# voice-card-controller-1_1-w-logo.net
KiCad netlist of a schematic drawn in EAGLE
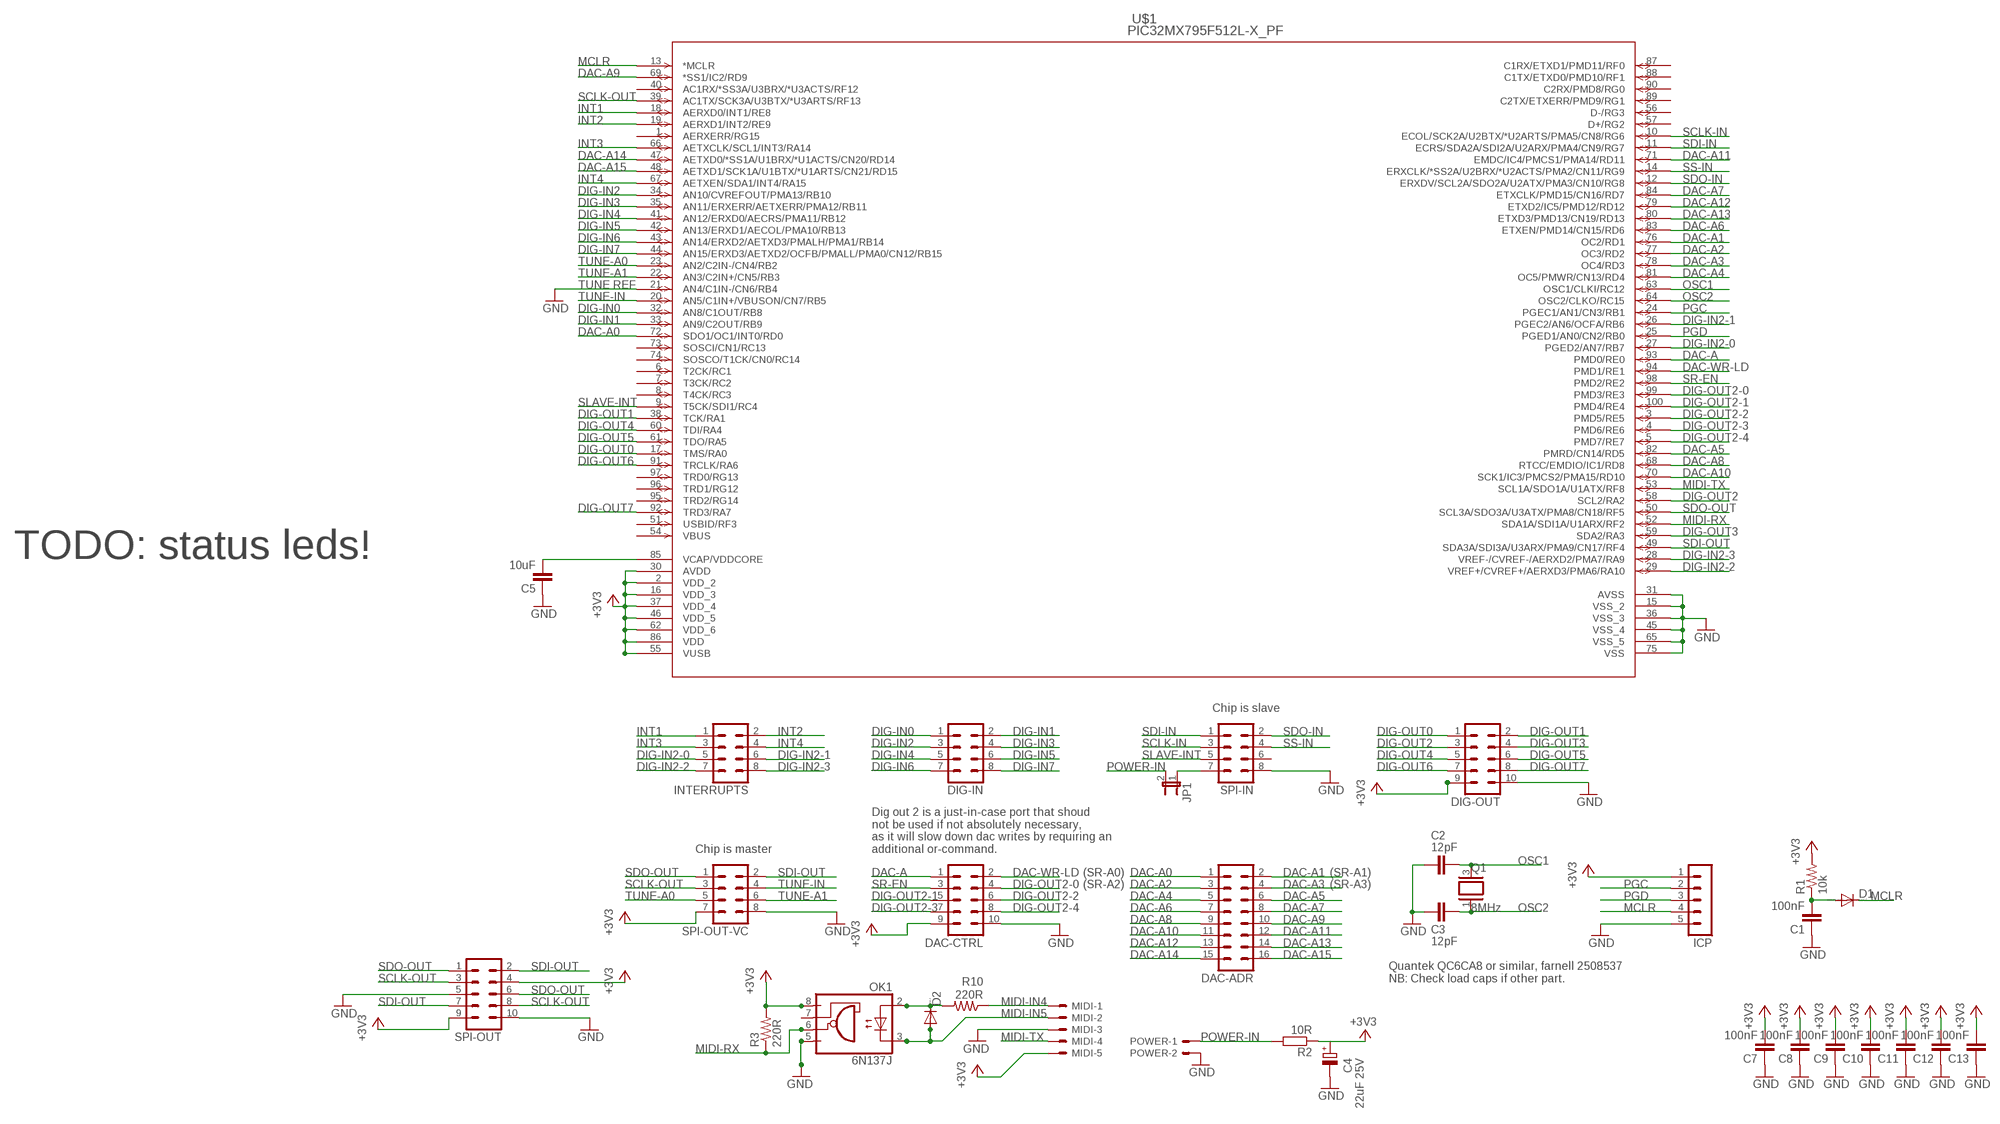
[diagram p0: schematic, sheet 1]

(export (version "E")
  (design (tool "Eeschema 10.0.6"))
  (components
    (comp (ref "C1")
      (value "100nF")
      (footprint "eagle-import:C0603")
      (libsource (lib "eagle-import") (part "C-EUC0603"))
    )
    (comp (ref "C2")
      (value "12pF")
      (footprint "eagle-import:C0603")
      (libsource (lib "eagle-import") (part "C-EUC0603"))
    )
    (comp (ref "C3")
      (value "12pF")
      (footprint "eagle-import:C0603")
      (libsource (lib "eagle-import") (part "C-EUC0603"))
    )
    (comp (ref "C4")
      (value "22uF 25V")
      (footprint "eagle-import:E2,5-5")
      (libsource (lib "eagle-import") (part "CPOL-EUE2.5-5"))
    )
    (comp (ref "C5")
      (value "10uF")
      (footprint "eagle-import:C0805")
      (libsource (lib "eagle-import") (part "C-EUC0805"))
    )
    (comp (ref "C7")
      (value "100nF")
      (footprint "eagle-import:C0603")
      (libsource (lib "eagle-import") (part "C-EUC0603"))
    )
    (comp (ref "C8")
      (value "100nF")
      (footprint "eagle-import:C0603")
      (libsource (lib "eagle-import") (part "C-EUC0603"))
    )
    (comp (ref "C9")
      (value "100nF")
      (footprint "eagle-import:C0603")
      (libsource (lib "eagle-import") (part "C-EUC0603"))
    )
    (comp (ref "C10")
      (value "100nF")
      (footprint "eagle-import:C0603")
      (libsource (lib "eagle-import") (part "C-EUC0603"))
    )
    (comp (ref "C11")
      (value "100nF")
      (footprint "eagle-import:C0603")
      (libsource (lib "eagle-import") (part "C-EUC0603"))
    )
    (comp (ref "C12")
      (value "100nF")
      (footprint "eagle-import:C0603")
      (libsource (lib "eagle-import") (part "C-EUC0603"))
    )
    (comp (ref "C13")
      (value "100nF")
      (footprint "eagle-import:C0603")
      (libsource (lib "eagle-import") (part "C-EUC0603"))
    )
    (comp (ref "D1")
      (value "DIODE-SOD80C")
      (footprint "eagle-import:SOD80C")
      (libsource (lib "eagle-import") (part "DIODE-SOD80C"))
    )
    (comp (ref "D2")
      (value "DIODE-SOD80C")
      (footprint "eagle-import:SOD80C")
      (libsource (lib "eagle-import") (part "DIODE-SOD80C"))
    )
    (comp (ref "DAC-ADR")
      (value "MA08-2J")
      (footprint "eagle-import:MA08-2J")
      (libsource (lib "eagle-import") (part "MA08-2J"))
    )
    (comp (ref "DAC-CTRL")
      (value "MA05-2J")
      (footprint "eagle-import:MA05-2J")
      (libsource (lib "eagle-import") (part "MA05-2J"))
    )
    (comp (ref "DIG-IN")
      (value "MA04-2J")
      (footprint "eagle-import:MA04-2J")
      (libsource (lib "eagle-import") (part "MA04-2J"))
    )
    (comp (ref "DIG-OUT")
      (value "MA05-2J")
      (footprint "eagle-import:MA05-2J")
      (libsource (lib "eagle-import") (part "MA05-2J"))
    )
    (comp (ref "ICP")
      (value "MA05-1")
      (footprint "eagle-import:MA05-1")
      (libsource (lib "eagle-import") (part "MA05-1"))
    )
    (comp (ref "INTERRUPTS")
      (value "MA04-2J")
      (footprint "eagle-import:MA04-2J")
      (libsource (lib "eagle-import") (part "MA04-2J"))
    )
    (comp (ref "JP1")
      (value "JP1E")
      (footprint "eagle-import:JP1")
      (libsource (lib "eagle-import") (part "JP1E"))
    )
    (comp (ref "MIDI")
      (value "22-23-2051")
      (footprint "eagle-import:22-23-2051")
      (fields (field (name "MF") "MOLEX"))
      (libsource (lib "eagle-import") (part "22-23-2051"))
    )
    (comp (ref "OK1")
      (value "6N137J")
      (footprint "eagle-import:DIL08-J")
      (libsource (lib "eagle-import") (part "6N137J"))
    )
    (comp (ref "POWER")
      (value "22-23-2021")
      (footprint "eagle-import:22-23-2021")
      (fields (field (name "MF") "MOLEX"))
      (libsource (lib "eagle-import") (part "22-23-2021"))
    )
    (comp (ref "Q1")
      (value "8MHz")
      (footprint "eagle-import:CTS406J")
      (libsource (lib "eagle-import") (part "XTAL-J"))
    )
    (comp (ref "R1")
      (value "10k")
      (footprint "eagle-import:R0805")
      (libsource (lib "eagle-import") (part "R-US_R0805"))
    )
    (comp (ref "R2")
      (value "10R")
      (footprint "eagle-import:0207_7")
      (libsource (lib "eagle-import") (part "R-EU_0207/7"))
    )
    (comp (ref "R3")
      (value "220R")
      (footprint "eagle-import:R0805")
      (libsource (lib "eagle-import") (part "R-US_R0805"))
    )
    (comp (ref "R10")
      (value "220R")
      (footprint "eagle-import:R0805")
      (libsource (lib "eagle-import") (part "R-US_R0805"))
    )
    (comp (ref "SPI-IN")
      (value "MA04-2J")
      (footprint "eagle-import:MA04-2J")
      (libsource (lib "eagle-import") (part "MA04-2J"))
    )
    (comp (ref "SPI-OUT")
      (value "MA05-2J")
      (footprint "eagle-import:MA05-2J")
      (libsource (lib "eagle-import") (part "MA05-2J"))
    )
    (comp (ref "SPI-OUT-VC")
      (value "MA04-2J")
      (footprint "eagle-import:MA04-2J")
      (libsource (lib "eagle-import") (part "MA04-2J"))
    )
    (comp (ref "U$1")
      (value "PIC32MX795F512L-X_PF")
      (footprint "eagle-import:TQFP100_14X14MC")
      (libsource (lib "eagle-import") (part "PIC32MX795F512L-X_PF"))
    )
  )
  (nets
    (net (code "1") (name "+3V3") (class "Default")
      (node (ref "C10") (pin "2") (pinfunction "2_2") (pintype "passive"))
      (node (ref "C11") (pin "2") (pinfunction "2_2") (pintype "passive"))
      (node (ref "C12") (pin "2") (pinfunction "2_2") (pintype "passive"))
      (node (ref "C13") (pin "2") (pinfunction "2_2") (pintype "passive"))
      (node (ref "C4") (pin "+") (pinfunction "+_+") (pintype "passive"))
      (node (ref "C7") (pin "2") (pinfunction "2_2") (pintype "passive"))
      (node (ref "C8") (pin "2") (pinfunction "2_2") (pintype "passive"))
      (node (ref "C9") (pin "2") (pinfunction "2_2") (pintype "passive"))
      (node (ref "DAC-CTRL") (pin "9") (pinfunction "9_9") (pintype "passive"))
      (node (ref "DIG-OUT") (pin "9") (pinfunction "9_9") (pintype "passive"))
      (node (ref "ICP") (pin "1") (pinfunction "1_1") (pintype "passive"))
      (node (ref "MIDI") (pin "5") (pinfunction "S_5") (pintype "passive"))
      (node (ref "OK1") (pin "8") (pinfunction "VCC_8") (pintype "passive"))
      (node (ref "R1") (pin "2") (pinfunction "2_2") (pintype "passive"))
      (node (ref "R2") (pin "1") (pinfunction "1_1") (pintype "passive"))
      (node (ref "R3") (pin "2") (pinfunction "2_2") (pintype "passive"))
      (node (ref "SPI-OUT") (pin "4") (pinfunction "4_4") (pintype "passive"))
      (node (ref "SPI-OUT") (pin "9") (pinfunction "9_9") (pintype "passive"))
      (node (ref "SPI-OUT-VC") (pin "7") (pinfunction "7_7") (pintype "passive"))
      (node (ref "U$1") (pin "16") (pinfunction "VDD_3_16") (pintype "power_in"))
      (node (ref "U$1") (pin "2") (pinfunction "VDD_2_2") (pintype "power_in"))
      (node (ref "U$1") (pin "30") (pinfunction "AVDD_30") (pintype "power_in"))
      (node (ref "U$1") (pin "37") (pinfunction "VDD_4_37") (pintype "power_in"))
      (node (ref "U$1") (pin "46") (pinfunction "VDD_5_46") (pintype "power_in"))
      (node (ref "U$1") (pin "55") (pinfunction "VUSB_55") (pintype "power_in"))
      (node (ref "U$1") (pin "62") (pinfunction "VDD_6_62") (pintype "power_in"))
      (node (ref "U$1") (pin "86") (pinfunction "VDD_86") (pintype "power_in"))
    )
    (net (code "2") (name "/DAC-A") (class "Default")
      (node (ref "DAC-CTRL") (pin "1") (pinfunction "1_1") (pintype "passive"))
      (node (ref "U$1") (pin "93") (pinfunction "PMD0/RE0_93") (pintype "bidirectional"))
    )
    (net (code "3") (name "/DAC-A0") (class "Default")
      (node (ref "DAC-ADR") (pin "1") (pinfunction "1_1") (pintype "passive"))
      (node (ref "U$1") (pin "72") (pinfunction "SDO1/OC1/INT0/RD0_72") (pintype "bidirectional"))
    )
    (net (code "4") (name "/DAC-A1") (class "Default")
      (node (ref "DAC-ADR") (pin "2") (pinfunction "2_2") (pintype "passive"))
      (node (ref "U$1") (pin "76") (pinfunction "OC2/RD1_76") (pintype "bidirectional"))
    )
    (net (code "5") (name "/DAC-A2") (class "Default")
      (node (ref "DAC-ADR") (pin "3") (pinfunction "3_3") (pintype "passive"))
      (node (ref "U$1") (pin "77") (pinfunction "OC3/RD2_77") (pintype "bidirectional"))
    )
    (net (code "6") (name "/DAC-A3") (class "Default")
      (node (ref "DAC-ADR") (pin "4") (pinfunction "4_4") (pintype "passive"))
      (node (ref "U$1") (pin "78") (pinfunction "OC4/RD3_78") (pintype "bidirectional"))
    )
    (net (code "7") (name "/DAC-A4") (class "Default")
      (node (ref "DAC-ADR") (pin "5") (pinfunction "5_5") (pintype "passive"))
      (node (ref "U$1") (pin "81") (pinfunction "OC5/PMWR/CN13/RD4_81") (pintype "bidirectional"))
    )
    (net (code "8") (name "/DAC-A5") (class "Default")
      (node (ref "DAC-ADR") (pin "6") (pinfunction "6_6") (pintype "passive"))
      (node (ref "U$1") (pin "82") (pinfunction "PMRD/CN14/RD5_82") (pintype "bidirectional"))
    )
    (net (code "9") (name "/DAC-A6") (class "Default")
      (node (ref "DAC-ADR") (pin "7") (pinfunction "7_7") (pintype "passive"))
      (node (ref "U$1") (pin "83") (pinfunction "ETXEN/PMD14/CN15/RD6_83") (pintype "bidirectional"))
    )
    (net (code "10") (name "/DAC-A7") (class "Default")
      (node (ref "DAC-ADR") (pin "8") (pinfunction "8_8") (pintype "passive"))
      (node (ref "U$1") (pin "84") (pinfunction "ETXCLK/PMD15/CN16/RD7_84") (pintype "bidirectional"))
    )
    (net (code "11") (name "/DAC-A8") (class "Default")
      (node (ref "DAC-ADR") (pin "9") (pinfunction "9_9") (pintype "passive"))
      (node (ref "U$1") (pin "68") (pinfunction "RTCC/EMDIO/IC1/RD8_68") (pintype "bidirectional"))
    )
    (net (code "12") (name "/DAC-A9") (class "Default")
      (node (ref "DAC-ADR") (pin "10") (pinfunction "10_10") (pintype "passive"))
      (node (ref "U$1") (pin "69") (pinfunction "*SS1/IC2/RD9_69") (pintype "bidirectional"))
    )
    (net (code "13") (name "/DAC-A10") (class "Default")
      (node (ref "DAC-ADR") (pin "11") (pinfunction "11_11") (pintype "passive"))
      (node (ref "U$1") (pin "70") (pinfunction "SCK1/IC3/PMCS2/PMA15/RD10_70") (pintype "bidirectional"))
    )
    (net (code "14") (name "/DAC-A11") (class "Default")
      (node (ref "DAC-ADR") (pin "12") (pinfunction "12_12") (pintype "passive"))
      (node (ref "U$1") (pin "71") (pinfunction "EMDC/IC4/PMCS1/PMA14/RD11_71") (pintype "bidirectional"))
    )
    (net (code "15") (name "/DAC-A12") (class "Default")
      (node (ref "DAC-ADR") (pin "13") (pinfunction "13_13") (pintype "passive"))
      (node (ref "U$1") (pin "79") (pinfunction "ETXD2/IC5/PMD12/RD12_79") (pintype "bidirectional"))
    )
    (net (code "16") (name "/DAC-A13") (class "Default")
      (node (ref "DAC-ADR") (pin "14") (pinfunction "14_14") (pintype "passive"))
      (node (ref "U$1") (pin "80") (pinfunction "ETXD3/PMD13/CN19/RD13_80") (pintype "bidirectional"))
    )
    (net (code "17") (name "/DAC-A14") (class "Default")
      (node (ref "DAC-ADR") (pin "15") (pinfunction "15_15") (pintype "passive"))
      (node (ref "U$1") (pin "47") (pinfunction "AETXD0/*SS1A/U1BRX/*U1ACTS/CN20/RD14_47") (pintype "bidirectional"))
    )
    (net (code "18") (name "/DAC-A15") (class "Default")
      (node (ref "DAC-ADR") (pin "16") (pinfunction "16_16") (pintype "passive"))
      (node (ref "U$1") (pin "48") (pinfunction "AETXD1/SCK1A/U1BTX/*U1ARTS/CN21/RD15_48") (pintype "bidirectional"))
    )
    (net (code "19") (name "/DAC-WR-LD") (class "Default")
      (node (ref "DAC-CTRL") (pin "2") (pinfunction "2_2") (pintype "passive"))
      (node (ref "U$1") (pin "94") (pinfunction "PMD1/RE1_94") (pintype "bidirectional"))
    )
    (net (code "20") (name "/DIG-IN0") (class "Default")
      (node (ref "DIG-IN") (pin "1") (pinfunction "1_1") (pintype "passive"))
      (node (ref "U$1") (pin "32") (pinfunction "AN8/C1OUT/RB8_32") (pintype "bidirectional"))
    )
    (net (code "21") (name "/DIG-IN1") (class "Default")
      (node (ref "DIG-IN") (pin "2") (pinfunction "2_2") (pintype "passive"))
      (node (ref "U$1") (pin "33") (pinfunction "AN9/C2OUT/RB9_33") (pintype "bidirectional"))
    )
    (net (code "22") (name "/DIG-IN2") (class "Default")
      (node (ref "DIG-IN") (pin "3") (pinfunction "3_3") (pintype "passive"))
      (node (ref "U$1") (pin "34") (pinfunction "AN10/CVREFOUT/PMA13/RB10_34") (pintype "bidirectional"))
    )
    (net (code "23") (name "/DIG-IN2-0") (class "Default")
      (node (ref "INTERRUPTS") (pin "5") (pinfunction "5_5") (pintype "passive"))
      (node (ref "U$1") (pin "27") (pinfunction "PGED2/AN7/RB7_27") (pintype "bidirectional"))
    )
    (net (code "24") (name "/DIG-IN2-1") (class "Default")
      (node (ref "INTERRUPTS") (pin "6") (pinfunction "6_6") (pintype "passive"))
      (node (ref "U$1") (pin "26") (pinfunction "PGEC2/AN6/OCFA/RB6_26") (pintype "bidirectional"))
    )
    (net (code "25") (name "/DIG-IN2-2") (class "Default")
      (node (ref "INTERRUPTS") (pin "7") (pinfunction "7_7") (pintype "passive"))
      (node (ref "U$1") (pin "29") (pinfunction "VREF+/CVREF+/AERXD3/PMA6/RA10_29") (pintype "bidirectional"))
    )
    (net (code "26") (name "/DIG-IN2-3") (class "Default")
      (node (ref "INTERRUPTS") (pin "8") (pinfunction "8_8") (pintype "passive"))
      (node (ref "U$1") (pin "28") (pinfunction "VREF-/CVREF-/AERXD2/PMA7/RA9_28") (pintype "bidirectional"))
    )
    (net (code "27") (name "/DIG-IN3") (class "Default")
      (node (ref "DIG-IN") (pin "4") (pinfunction "4_4") (pintype "passive"))
      (node (ref "U$1") (pin "35") (pinfunction "AN11/ERXERR/AETXERR/PMA12/RB11_35") (pintype "bidirectional"))
    )
    (net (code "28") (name "/DIG-IN4") (class "Default")
      (node (ref "DIG-IN") (pin "5") (pinfunction "5_5") (pintype "passive"))
      (node (ref "U$1") (pin "41") (pinfunction "AN12/ERXD0/AECRS/PMA11/RB12_41") (pintype "bidirectional"))
    )
    (net (code "29") (name "/DIG-IN5") (class "Default")
      (node (ref "DIG-IN") (pin "6") (pinfunction "6_6") (pintype "passive"))
      (node (ref "U$1") (pin "42") (pinfunction "AN13/ERXD1/AECOL/PMA10/RB13_42") (pintype "bidirectional"))
    )
    (net (code "30") (name "/DIG-IN6") (class "Default")
      (node (ref "DIG-IN") (pin "7") (pinfunction "7_7") (pintype "passive"))
      (node (ref "U$1") (pin "43") (pinfunction "AN14/ERXD2/AETXD3/PMALH/PMA1/RB14_43") (pintype "bidirectional"))
    )
    (net (code "31") (name "/DIG-IN7") (class "Default")
      (node (ref "DIG-IN") (pin "8") (pinfunction "8_8") (pintype "passive"))
      (node (ref "U$1") (pin "44") (pinfunction "AN15/ERXD3/AETXD2/OCFB/PMALL/PMA0/CN12/RB15_44") (pintype "bidirectional"))
    )
    (net (code "32") (name "/DIG-OUT0") (class "Default")
      (node (ref "DIG-OUT") (pin "1") (pinfunction "1_1") (pintype "passive"))
      (node (ref "U$1") (pin "17") (pinfunction "TMS/RA0_17") (pintype "bidirectional"))
    )
    (net (code "33") (name "/DIG-OUT1") (class "Default")
      (node (ref "DIG-OUT") (pin "2") (pinfunction "2_2") (pintype "passive"))
      (node (ref "U$1") (pin "38") (pinfunction "TCK/RA1_38") (pintype "bidirectional"))
    )
    (net (code "34") (name "/DIG-OUT2") (class "Default")
      (node (ref "DIG-OUT") (pin "3") (pinfunction "3_3") (pintype "passive"))
      (node (ref "U$1") (pin "58") (pinfunction "SCL2/RA2_58") (pintype "bidirectional"))
    )
    (net (code "35") (name "/DIG-OUT2-0") (class "Default")
      (node (ref "DAC-CTRL") (pin "4") (pinfunction "4_4") (pintype "passive"))
      (node (ref "U$1") (pin "99") (pinfunction "PMD3/RE3_99") (pintype "bidirectional"))
    )
    (net (code "36") (name "/DIG-OUT2-1") (class "Default")
      (node (ref "DAC-CTRL") (pin "5") (pinfunction "5_5") (pintype "passive"))
      (node (ref "U$1") (pin "100") (pinfunction "PMD4/RE4_100") (pintype "bidirectional"))
    )
    (net (code "37") (name "/DIG-OUT2-2") (class "Default")
      (node (ref "DAC-CTRL") (pin "6") (pinfunction "6_6") (pintype "passive"))
      (node (ref "U$1") (pin "3") (pinfunction "PMD5/RE5_3") (pintype "bidirectional"))
    )
    (net (code "38") (name "/DIG-OUT2-3") (class "Default")
      (node (ref "DAC-CTRL") (pin "7") (pinfunction "7_7") (pintype "passive"))
      (node (ref "U$1") (pin "4") (pinfunction "PMD6/RE6_4") (pintype "bidirectional"))
    )
    (net (code "39") (name "/DIG-OUT2-4") (class "Default")
      (node (ref "DAC-CTRL") (pin "8") (pinfunction "8_8") (pintype "passive"))
      (node (ref "U$1") (pin "5") (pinfunction "PMD7/RE7_5") (pintype "bidirectional"))
    )
    (net (code "40") (name "/DIG-OUT3") (class "Default")
      (node (ref "DIG-OUT") (pin "4") (pinfunction "4_4") (pintype "passive"))
      (node (ref "U$1") (pin "59") (pinfunction "SDA2/RA3_59") (pintype "bidirectional"))
    )
    (net (code "41") (name "/DIG-OUT4") (class "Default")
      (node (ref "DIG-OUT") (pin "5") (pinfunction "5_5") (pintype "passive"))
      (node (ref "U$1") (pin "60") (pinfunction "TDI/RA4_60") (pintype "bidirectional"))
    )
    (net (code "42") (name "/DIG-OUT5") (class "Default")
      (node (ref "DIG-OUT") (pin "6") (pinfunction "6_6") (pintype "passive"))
      (node (ref "U$1") (pin "61") (pinfunction "TDO/RA5_61") (pintype "bidirectional"))
    )
    (net (code "43") (name "/DIG-OUT6") (class "Default")
      (node (ref "DIG-OUT") (pin "7") (pinfunction "7_7") (pintype "passive"))
      (node (ref "U$1") (pin "91") (pinfunction "TRCLK/RA6_91") (pintype "bidirectional"))
    )
    (net (code "44") (name "/DIG-OUT7") (class "Default")
      (node (ref "DIG-OUT") (pin "8") (pinfunction "8_8") (pintype "passive"))
      (node (ref "U$1") (pin "92") (pinfunction "TRD3/RA7_92") (pintype "bidirectional"))
    )
    (net (code "45") (name "/INT1") (class "Default")
      (node (ref "INTERRUPTS") (pin "1") (pinfunction "1_1") (pintype "passive"))
      (node (ref "U$1") (pin "18") (pinfunction "AERXD0/INT1/RE8_18") (pintype "bidirectional"))
    )
    (net (code "46") (name "/INT2") (class "Default")
      (node (ref "INTERRUPTS") (pin "2") (pinfunction "2_2") (pintype "passive"))
      (node (ref "U$1") (pin "19") (pinfunction "AERXD1/INT2/RE9_19") (pintype "bidirectional"))
    )
    (net (code "47") (name "/INT3") (class "Default")
      (node (ref "INTERRUPTS") (pin "3") (pinfunction "3_3") (pintype "passive"))
      (node (ref "U$1") (pin "66") (pinfunction "AETXCLK/SCL1/INT3/RA14_66") (pintype "bidirectional"))
    )
    (net (code "48") (name "/INT4") (class "Default")
      (node (ref "INTERRUPTS") (pin "4") (pinfunction "4_4") (pintype "passive"))
      (node (ref "U$1") (pin "67") (pinfunction "AETXEN/SDA1/INT4/RA15_67") (pintype "bidirectional"))
    )
    (net (code "49") (name "/MCLR") (class "Default")
      (node (ref "D1") (pin "C") (pinfunction "C_C") (pintype "passive"))
      (node (ref "ICP") (pin "4") (pinfunction "4_4") (pintype "passive"))
      (node (ref "U$1") (pin "13") (pinfunction "*MCLR_13") (pintype "input"))
    )
    (net (code "50") (name "/MIDI-IN4") (class "Default")
      (node (ref "MIDI") (pin "1") (pinfunction "S_1") (pintype "passive"))
      (node (ref "R10") (pin "1") (pinfunction "1_1") (pintype "passive"))
    )
    (net (code "51") (name "/MIDI-IN5") (class "Default")
      (node (ref "D2") (pin "A") (pinfunction "A_A") (pintype "passive"))
      (node (ref "MIDI") (pin "2") (pinfunction "S_2") (pintype "passive"))
      (node (ref "OK1") (pin "3") (pinfunction "C_3") (pintype "passive"))
    )
    (net (code "52") (name "/MIDI-RX") (class "Default")
      (node (ref "OK1") (pin "6") (pinfunction "VO_6") (pintype "passive"))
      (node (ref "R3") (pin "1") (pinfunction "1_1") (pintype "passive"))
      (node (ref "U$1") (pin "52") (pinfunction "SDA1A/SDI1A/U1ARX/RF2_52") (pintype "bidirectional"))
    )
    (net (code "53") (name "/MIDI-TX") (class "Default")
      (node (ref "MIDI") (pin "4") (pinfunction "S_4") (pintype "passive"))
      (node (ref "U$1") (pin "53") (pinfunction "SCL1A/SDO1A/U1ATX/RF8_53") (pintype "bidirectional"))
    )
    (net (code "54") (name "/OSC1") (class "Default")
      (node (ref "C2") (pin "1") (pinfunction "1_1") (pintype "passive"))
      (node (ref "Q1") (pin "3") (pinfunction "2_3") (pintype "passive"))
      (node (ref "U$1") (pin "63") (pinfunction "OSC1/CLKI/RC12_63") (pintype "bidirectional"))
    )
    (net (code "55") (name "/OSC2") (class "Default")
      (node (ref "C3") (pin "1") (pinfunction "1_1") (pintype "passive"))
      (node (ref "Q1") (pin "1") (pinfunction "1_1") (pintype "passive"))
      (node (ref "U$1") (pin "64") (pinfunction "OSC2/CLKO/RC15_64") (pintype "bidirectional"))
    )
    (net (code "56") (name "/PGC") (class "Default")
      (node (ref "ICP") (pin "2") (pinfunction "2_2") (pintype "passive"))
      (node (ref "U$1") (pin "24") (pinfunction "PGEC1/AN1/CN3/RB1_24") (pintype "bidirectional"))
    )
    (net (code "57") (name "/PGD") (class "Default")
      (node (ref "ICP") (pin "3") (pinfunction "3_3") (pintype "passive"))
      (node (ref "U$1") (pin "25") (pinfunction "PGED1/AN0/CN2/RB0_25") (pintype "bidirectional"))
    )
    (net (code "58") (name "/POWER-IN") (class "Default")
      (node (ref "JP1") (pin "2") (pinfunction "2_2") (pintype "passive"))
      (node (ref "POWER") (pin "1") (pinfunction "S_1") (pintype "passive"))
      (node (ref "R2") (pin "2") (pinfunction "2_2") (pintype "passive"))
    )
    (net (code "59") (name "/SCLK-IN") (class "Default")
      (node (ref "SPI-IN") (pin "3") (pinfunction "3_3") (pintype "passive"))
      (node (ref "U$1") (pin "10") (pinfunction "ECOL/SCK2A/U2BTX/*U2ARTS/PMA5/CN8/RG6_10") (pintype "bidirectional"))
    )
    (net (code "60") (name "/SCLK-OUT") (class "Default")
      (node (ref "SPI-OUT") (pin "3") (pinfunction "3_3") (pintype "passive"))
      (node (ref "SPI-OUT") (pin "8") (pinfunction "8_8") (pintype "passive"))
      (node (ref "SPI-OUT-VC") (pin "3") (pinfunction "3_3") (pintype "passive"))
      (node (ref "U$1") (pin "39") (pinfunction "AC1TX/SCK3A/U3BTX/*U3ARTS/RF13_39") (pintype "bidirectional"))
    )
    (net (code "61") (name "/SDI-IN") (class "Default")
      (node (ref "SPI-IN") (pin "1") (pinfunction "1_1") (pintype "passive"))
      (node (ref "U$1") (pin "11") (pinfunction "ECRS/SDA2A/SDI2A/U2ARX/PMA4/CN9/RG7_11") (pintype "bidirectional"))
    )
    (net (code "62") (name "/SDI-OUT") (class "Default")
      (node (ref "SPI-OUT") (pin "2") (pinfunction "2_2") (pintype "passive"))
      (node (ref "SPI-OUT") (pin "7") (pinfunction "7_7") (pintype "passive"))
      (node (ref "SPI-OUT-VC") (pin "2") (pinfunction "2_2") (pintype "passive"))
      (node (ref "U$1") (pin "49") (pinfunction "SDA3A/SDI3A/U3ARX/PMA9/CN17/RF4_49") (pintype "bidirectional"))
    )
    (net (code "63") (name "/SDO-IN") (class "Default")
      (node (ref "SPI-IN") (pin "2") (pinfunction "2_2") (pintype "passive"))
      (node (ref "U$1") (pin "12") (pinfunction "ERXDV/SCL2A/SDO2A/U2ATX/PMA3/CN10/RG8_12") (pintype "bidirectional"))
    )
    (net (code "64") (name "/SDO-OUT") (class "Default")
      (node (ref "SPI-OUT") (pin "1") (pinfunction "1_1") (pintype "passive"))
      (node (ref "SPI-OUT") (pin "6") (pinfunction "6_6") (pintype "passive"))
      (node (ref "SPI-OUT-VC") (pin "1") (pinfunction "1_1") (pintype "passive"))
      (node (ref "U$1") (pin "50") (pinfunction "SCL3A/SDO3A/U3ATX/PMA8/CN18/RF5_50") (pintype "bidirectional"))
    )
    (net (code "65") (name "/SLAVE-INT") (class "Default")
      (node (ref "SPI-IN") (pin "5") (pinfunction "5_5") (pintype "passive"))
      (node (ref "U$1") (pin "9") (pinfunction "T5CK/SDI1/RC4_9") (pintype "bidirectional"))
    )
    (net (code "66") (name "/SR-EN") (class "Default")
      (node (ref "DAC-CTRL") (pin "3") (pinfunction "3_3") (pintype "passive"))
      (node (ref "U$1") (pin "98") (pinfunction "PMD2/RE2_98") (pintype "bidirectional"))
    )
    (net (code "67") (name "/SS-IN") (class "Default")
      (node (ref "SPI-IN") (pin "4") (pinfunction "4_4") (pintype "passive"))
      (node (ref "U$1") (pin "14") (pinfunction "ERXCLK/*SS2A/U2BRX/*U2ACTS/PMA2/CN11/RG9_14") (pintype "bidirectional"))
    )
    (net (code "68") (name "/TUNE-A0") (class "Default")
      (node (ref "SPI-OUT-VC") (pin "5") (pinfunction "5_5") (pintype "passive"))
      (node (ref "U$1") (pin "23") (pinfunction "AN2/C2IN-/CN4/RB2_23") (pintype "bidirectional"))
    )
    (net (code "69") (name "/TUNE-A1") (class "Default")
      (node (ref "SPI-OUT-VC") (pin "6") (pinfunction "6_6") (pintype "passive"))
      (node (ref "U$1") (pin "22") (pinfunction "AN3/C2IN+/CN5/RB3_22") (pintype "bidirectional"))
    )
    (net (code "70") (name "/TUNE-IN") (class "Default")
      (node (ref "SPI-OUT-VC") (pin "4") (pinfunction "4_4") (pintype "passive"))
      (node (ref "U$1") (pin "20") (pinfunction "AN5/C1IN+/VBUSON/CN7/RB5_20") (pintype "bidirectional"))
    )
    (net (code "71") (name "GND") (class "Default")
      (node (ref "C1") (pin "1") (pinfunction "1_1") (pintype "passive"))
      (node (ref "C10") (pin "1") (pinfunction "1_1") (pintype "passive"))
      (node (ref "C11") (pin "1") (pinfunction "1_1") (pintype "passive"))
      (node (ref "C12") (pin "1") (pinfunction "1_1") (pintype "passive"))
      (node (ref "C13") (pin "1") (pinfunction "1_1") (pintype "passive"))
      (node (ref "C2") (pin "2") (pinfunction "2_2") (pintype "passive"))
      (node (ref "C3") (pin "2") (pinfunction "2_2") (pintype "passive"))
      (node (ref "C4") (pin "-") (pinfunction "-_-") (pintype "passive"))
      (node (ref "C5") (pin "1") (pinfunction "1_1") (pintype "passive"))
      (node (ref "C7") (pin "1") (pinfunction "1_1") (pintype "passive"))
      (node (ref "C8") (pin "1") (pinfunction "1_1") (pintype "passive"))
      (node (ref "C9") (pin "1") (pinfunction "1_1") (pintype "passive"))
      (node (ref "DAC-CTRL") (pin "10") (pinfunction "10_10") (pintype "passive"))
      (node (ref "DIG-OUT") (pin "10") (pinfunction "10_10") (pintype "passive"))
      (node (ref "ICP") (pin "5") (pinfunction "5_5") (pintype "passive"))
      (node (ref "MIDI") (pin "3") (pinfunction "S_3") (pintype "passive"))
      (node (ref "OK1") (pin "5") (pinfunction "GND_5") (pintype "passive"))
      (node (ref "POWER") (pin "2") (pinfunction "S_2") (pintype "passive"))
      (node (ref "SPI-IN") (pin "8") (pinfunction "8_8") (pintype "passive"))
      (node (ref "SPI-OUT") (pin "10") (pinfunction "10_10") (pintype "passive"))
      (node (ref "SPI-OUT") (pin "5") (pinfunction "5_5") (pintype "passive"))
      (node (ref "SPI-OUT-VC") (pin "8") (pinfunction "8_8") (pintype "passive"))
      (node (ref "U$1") (pin "15") (pinfunction "VSS_2_15") (pintype "power_in"))
      (node (ref "U$1") (pin "21") (pinfunction "AN4/C1IN-/CN6/RB4_21") (pintype "bidirectional"))
      (node (ref "U$1") (pin "31") (pinfunction "AVSS_31") (pintype "power_in"))
      (node (ref "U$1") (pin "36") (pinfunction "VSS_3_36") (pintype "power_in"))
      (node (ref "U$1") (pin "45") (pinfunction "VSS_4_45") (pintype "power_in"))
      (node (ref "U$1") (pin "65") (pinfunction "VSS_5_65") (pintype "power_in"))
      (node (ref "U$1") (pin "75") (pinfunction "VSS_75") (pintype "power_in"))
    )
    (net (code "72") (name "Net-(C1-Pad2)") (class "Default")
      (node (ref "C1") (pin "2") (pinfunction "2_2") (pintype "passive"))
      (node (ref "D1") (pin "A") (pinfunction "A_A") (pintype "passive"))
      (node (ref "R1") (pin "1") (pinfunction "1_1") (pintype "passive"))
    )
    (net (code "73") (name "Net-(JP1-Pad1)") (class "Default")
      (node (ref "JP1") (pin "1") (pinfunction "1_1") (pintype "passive"))
      (node (ref "SPI-IN") (pin "7") (pinfunction "7_7") (pintype "passive"))
    )
    (net (code "74") (name "Net-(OK1-A)") (class "Default")
      (node (ref "D2") (pin "C") (pinfunction "C_C") (pintype "passive"))
      (node (ref "OK1") (pin "2") (pinfunction "A_2") (pintype "passive"))
      (node (ref "R10") (pin "2") (pinfunction "2_2") (pintype "passive"))
    )
    (net (code "75") (name "Net-(U$1-VCAP{slash}VDDCORE)") (class "Default")
      (node (ref "C5") (pin "2") (pinfunction "2_2") (pintype "passive"))
      (node (ref "U$1") (pin "85") (pinfunction "VCAP/VDDCORE_85") (pintype "power_in"))
    )
    (net (code "76") (name "unconnected-(OK1-VE-Pad7)") (class "Default")
      (node (ref "OK1") (pin "7") (pinfunction "VE_7") (pintype "passive"))
    )
    (net (code "77") (name "unconnected-(SPI-IN-Pad6)") (class "Default")
      (node (ref "SPI-IN") (pin "6") (pinfunction "6_6") (pintype "passive"))
    )
    (net (code "78") (name "unconnected-(U$1-AC1RX{slash}*SS3A{slash}U3BRX{slash}*U3ACTS{slash}RF12-Pad40)") (class "Default")
      (node (ref "U$1") (pin "40") (pinfunction "AC1RX/*SS3A/U3BRX/*U3ACTS/RF12_40") (pintype "bidirectional"))
    )
    (net (code "79") (name "unconnected-(U$1-AERXERR{slash}RG15-Pad1)") (class "Default")
      (node (ref "U$1") (pin "1") (pinfunction "AERXERR/RG15_1") (pintype "bidirectional"))
    )
    (net (code "80") (name "unconnected-(U$1-C1RX{slash}ETXD1{slash}PMD11{slash}RF0-Pad87)") (class "Default")
      (node (ref "U$1") (pin "87") (pinfunction "C1RX/ETXD1/PMD11/RF0_87") (pintype "bidirectional"))
    )
    (net (code "81") (name "unconnected-(U$1-C1TX{slash}ETXD0{slash}PMD10{slash}RF1-Pad88)") (class "Default")
      (node (ref "U$1") (pin "88") (pinfunction "C1TX/ETXD0/PMD10/RF1_88") (pintype "bidirectional"))
    )
    (net (code "82") (name "unconnected-(U$1-C2RX{slash}PMD8{slash}RG0-Pad90)") (class "Default")
      (node (ref "U$1") (pin "90") (pinfunction "C2RX/PMD8/RG0_90") (pintype "bidirectional"))
    )
    (net (code "83") (name "unconnected-(U$1-C2TX{slash}ETXERR{slash}PMD9{slash}RG1-Pad89)") (class "Default")
      (node (ref "U$1") (pin "89") (pinfunction "C2TX/ETXERR/PMD9/RG1_89") (pintype "bidirectional"))
    )
    (net (code "84") (name "unconnected-(U$1-D+{slash}RG2-Pad57)") (class "Default")
      (node (ref "U$1") (pin "57") (pinfunction "D+/RG2_57") (pintype "bidirectional"))
    )
    (net (code "85") (name "unconnected-(U$1-D-{slash}RG3-Pad56)") (class "Default")
      (node (ref "U$1") (pin "56") (pinfunction "D-/RG3_56") (pintype "bidirectional"))
    )
    (net (code "86") (name "unconnected-(U$1-SOSCI{slash}CN1{slash}RC13-Pad73)") (class "Default")
      (node (ref "U$1") (pin "73") (pinfunction "SOSCI/CN1/RC13_73") (pintype "bidirectional"))
    )
    (net (code "87") (name "unconnected-(U$1-SOSCO{slash}T1CK{slash}CN0{slash}RC14-Pad74)") (class "Default")
      (node (ref "U$1") (pin "74") (pinfunction "SOSCO/T1CK/CN0/RC14_74") (pintype "bidirectional"))
    )
    (net (code "88") (name "unconnected-(U$1-T2CK{slash}RC1-Pad6)") (class "Default")
      (node (ref "U$1") (pin "6") (pinfunction "T2CK/RC1_6") (pintype "bidirectional"))
    )
    (net (code "89") (name "unconnected-(U$1-T3CK{slash}RC2-Pad7)") (class "Default")
      (node (ref "U$1") (pin "7") (pinfunction "T3CK/RC2_7") (pintype "bidirectional"))
    )
    (net (code "90") (name "unconnected-(U$1-T4CK{slash}RC3-Pad8)") (class "Default")
      (node (ref "U$1") (pin "8") (pinfunction "T4CK/RC3_8") (pintype "bidirectional"))
    )
    (net (code "91") (name "unconnected-(U$1-TRD0{slash}RG13-Pad97)") (class "Default")
      (node (ref "U$1") (pin "97") (pinfunction "TRD0/RG13_97") (pintype "bidirectional"))
    )
    (net (code "92") (name "unconnected-(U$1-TRD1{slash}RG12-Pad96)") (class "Default")
      (node (ref "U$1") (pin "96") (pinfunction "TRD1/RG12_96") (pintype "bidirectional"))
    )
    (net (code "93") (name "unconnected-(U$1-TRD2{slash}RG14-Pad95)") (class "Default")
      (node (ref "U$1") (pin "95") (pinfunction "TRD2/RG14_95") (pintype "bidirectional"))
    )
    (net (code "94") (name "unconnected-(U$1-USBID{slash}RF3-Pad51)") (class "Default")
      (node (ref "U$1") (pin "51") (pinfunction "USBID/RF3_51") (pintype "bidirectional"))
    )
    (net (code "95") (name "unconnected-(U$1-VBUS-Pad54)") (class "Default")
      (node (ref "U$1") (pin "54") (pinfunction "VBUS_54") (pintype "input"))
    )
  )
)
